# cpu.net
KiCad netlist of a schematic drawn in Altium Designer
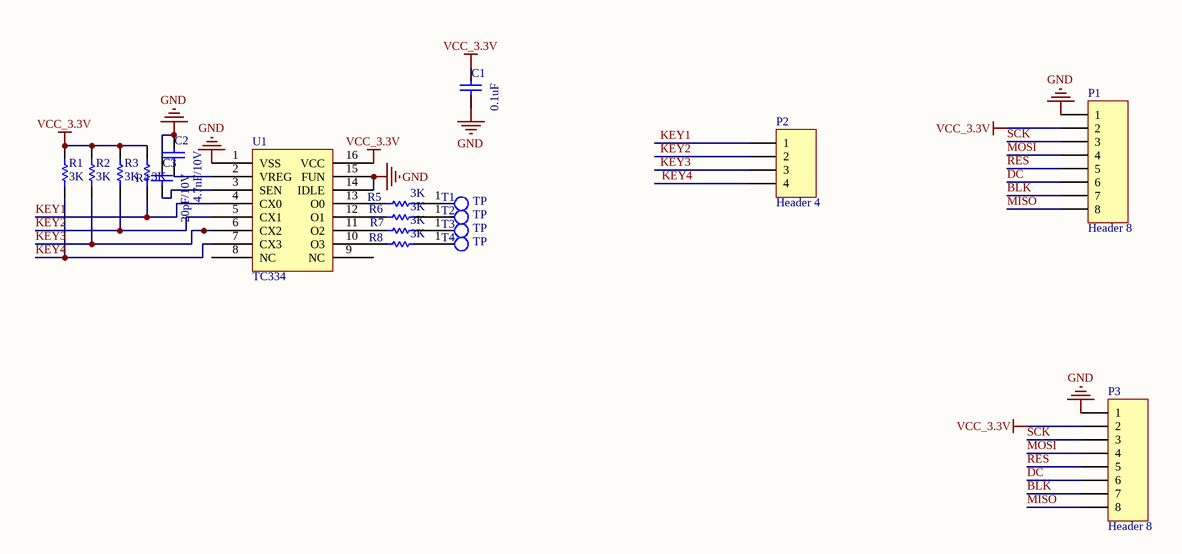
[diagram p0: cpu.SchDoc]

(export (version "E")
  (design (tool "Eeschema 10.0.6"))
  (components
    (comp (ref "C1")
      (value "0.1uF")
      (footprint "0603C")
      (description "Capacitor")
      (fields (field (name "PUBLISHER") "Altium Limited"))
      (libsource (lib "Miscellaneous Devices") (part "Cap"))
    )
    (comp (ref "C2")
      (value "4.7nF/10V")
      (footprint "0603C")
      (description "Capacitor")
      (fields (field (name "PUBLISHER") "Altium Limited"))
      (libsource (lib "Miscellaneous Devices") (part "Cap"))
    )
    (comp (ref "C3")
      (value "20pF/10V")
      (footprint "0603C")
      (description "Capacitor")
      (fields (field (name "PUBLISHER") "Altium Limited"))
      (libsource (lib "Miscellaneous Devices") (part "Cap"))
    )
    (comp (ref "P1")
      (value "Header 8")
      (footprint "HDR1X8")
      (description "Header, 8-Pin")
      (fields (field (name "PUBLISHER") "Altium Limited"))
      (libsource (lib "Miscellaneous Connectors") (part "Header 8"))
    )
    (comp (ref "P2")
      (value "Header 4")
      (footprint "HDR1X4")
      (description "Header, 4-Pin")
      (fields (field (name "PUBLISHER") "Altium Limited"))
      (libsource (lib "Miscellaneous Connectors") (part "Header 4"))
    )
    (comp (ref "P3")
      (value "Header 8")
      (footprint "TFT2.4")
      (description "Header, 8-Pin")
      (fields (field (name "PUBLISHER") "Altium Limited"))
      (libsource (lib "Miscellaneous Connectors") (part "Header 8"))
    )
    (comp (ref "R1")
      (value "3K")
      (footprint "0603R")
      (description "Semiconductor Resistor")
      (fields (field (name "PUBLISHER") "Altium Limited"))
      (libsource (lib "Miscellaneous Devices") (part "Res Semi"))
    )
    (comp (ref "R2")
      (value "3K")
      (footprint "0603R")
      (description "Semiconductor Resistor")
      (fields (field (name "PUBLISHER") "Altium Limited"))
      (libsource (lib "Miscellaneous Devices") (part "Res Semi"))
    )
    (comp (ref "R3")
      (value "3K")
      (footprint "0603R")
      (description "Semiconductor Resistor")
      (fields (field (name "PUBLISHER") "Altium Limited"))
      (libsource (lib "Miscellaneous Devices") (part "Res Semi"))
    )
    (comp (ref "R4")
      (value "3K")
      (footprint "0603R")
      (description "Semiconductor Resistor")
      (fields (field (name "PUBLISHER") "Altium Limited"))
      (libsource (lib "Miscellaneous Devices") (part "Res Semi"))
    )
    (comp (ref "R5")
      (value "3K")
      (footprint "0603R")
      (description "Semiconductor Resistor")
      (fields (field (name "PUBLISHER") "Altium Limited"))
      (libsource (lib "Miscellaneous Devices") (part "Res Semi"))
    )
    (comp (ref "R6")
      (value "3K")
      (footprint "0603R")
      (description "Semiconductor Resistor")
      (fields (field (name "PUBLISHER") "Altium Limited"))
      (libsource (lib "Miscellaneous Devices") (part "Res Semi"))
    )
    (comp (ref "R7")
      (value "3K")
      (footprint "0603R")
      (description "Semiconductor Resistor")
      (fields (field (name "PUBLISHER") "Altium Limited"))
      (libsource (lib "Miscellaneous Devices") (part "Res Semi"))
    )
    (comp (ref "R8")
      (value "3K")
      (footprint "0603R")
      (description "Semiconductor Resistor")
      (fields (field (name "PUBLISHER") "Altium Limited"))
      (libsource (lib "Miscellaneous Devices") (part "Res Semi"))
    )
    (comp (ref "T1") (value "TP") (footprint "TOUCH-PAD") (libsource (lib "Schlib_20110825") (part "TP")))
    (comp (ref "T2") (value "TP") (footprint "TOUCH-PAD") (libsource (lib "Schlib_20110825") (part "TP")))
    (comp (ref "T3") (value "TP") (footprint "TOUCH-PAD") (libsource (lib "Schlib_20110825") (part "TP")))
    (comp (ref "T4") (value "TP") (footprint "TOUCH-PAD") (libsource (lib "Schlib_20110825") (part "TP")))
    (comp (ref "U1")
      (value "TC334")
      (footprint "SOIC127P600X265-16N")
      (libsource (lib "Schlib_20110825") (part "TC334"))
    )
  )
  (nets
    (net (code "1") (name "/BLK") (class "Default")
      (node (ref "P1") (pin "7") (pinfunction "7_7") (pintype "passive"))
      (node (ref "P3") (pin "7") (pinfunction "7_7") (pintype "passive"))
    )
    (net (code "2") (name "/DC") (class "Default")
      (node (ref "P1") (pin "6") (pinfunction "6_6") (pintype "passive"))
      (node (ref "P3") (pin "6") (pinfunction "6_6") (pintype "passive"))
    )
    (net (code "3") (name "/KEY1") (class "Default")
      (node (ref "P2") (pin "1") (pinfunction "1_1") (pintype "passive"))
      (node (ref "R4") (pin "2") (pinfunction "2_2") (pintype "passive"))
      (node (ref "U1") (pin "4") (pinfunction "CX0_4") (pintype "passive"))
    )
    (net (code "4") (name "/KEY2") (class "Default")
      (node (ref "P2") (pin "2") (pinfunction "2_2") (pintype "passive"))
      (node (ref "R3") (pin "2") (pinfunction "2_2") (pintype "passive"))
      (node (ref "U1") (pin "5") (pinfunction "CX1_5") (pintype "passive"))
    )
    (net (code "5") (name "/KEY3") (class "Default")
      (node (ref "P2") (pin "3") (pinfunction "3_3") (pintype "passive"))
      (node (ref "R2") (pin "2") (pinfunction "2_2") (pintype "passive"))
      (node (ref "U1") (pin "6") (pinfunction "CX2_6") (pintype "passive"))
    )
    (net (code "6") (name "/KEY4") (class "Default")
      (node (ref "P2") (pin "4") (pinfunction "4_4") (pintype "passive"))
      (node (ref "R1") (pin "2") (pinfunction "2_2") (pintype "passive"))
      (node (ref "U1") (pin "7") (pinfunction "CX3_7") (pintype "passive"))
    )
    (net (code "7") (name "/MISO") (class "Default")
      (node (ref "P1") (pin "8") (pinfunction "8_8") (pintype "passive"))
      (node (ref "P3") (pin "8") (pinfunction "8_8") (pintype "passive"))
    )
    (net (code "8") (name "/MOSI") (class "Default")
      (node (ref "P1") (pin "4") (pinfunction "4_4") (pintype "passive"))
      (node (ref "P3") (pin "4") (pinfunction "4_4") (pintype "passive"))
    )
    (net (code "9") (name "/RES") (class "Default")
      (node (ref "P1") (pin "5") (pinfunction "5_5") (pintype "passive"))
      (node (ref "P3") (pin "5") (pinfunction "5_5") (pintype "passive"))
    )
    (net (code "10") (name "/SCK") (class "Default")
      (node (ref "P1") (pin "3") (pinfunction "3_3") (pintype "passive"))
      (node (ref "P3") (pin "3") (pinfunction "3_3") (pintype "passive"))
    )
    (net (code "11") (name "GND") (class "Default")
      (node (ref "C1") (pin "2") (pinfunction "2_2") (pintype "passive"))
      (node (ref "C2") (pin "1") (pinfunction "1_1") (pintype "passive"))
      (node (ref "C3") (pin "1") (pinfunction "1_1") (pintype "passive"))
      (node (ref "P1") (pin "1") (pinfunction "1_1") (pintype "passive"))
      (node (ref "P3") (pin "1") (pinfunction "1_1") (pintype "passive"))
      (node (ref "U1") (pin "1") (pinfunction "VSS_1") (pintype "passive"))
      (node (ref "U1") (pin "14") (pinfunction "IDLE_14") (pintype "passive"))
      (node (ref "U1") (pin "15") (pinfunction "FUN_15") (pintype "passive"))
    )
    (net (code "12") (name "Net-(R5-Pad1)") (class "Default")
      (node (ref "R5") (pin "1") (pinfunction "1_1") (pintype "passive"))
      (node (ref "T1") (pin "1") (pintype "passive"))
    )
    (net (code "13") (name "Net-(R6-Pad1)") (class "Default")
      (node (ref "R6") (pin "1") (pinfunction "1_1") (pintype "passive"))
      (node (ref "T2") (pin "1") (pintype "passive"))
    )
    (net (code "14") (name "Net-(R7-Pad1)") (class "Default")
      (node (ref "R7") (pin "1") (pinfunction "1_1") (pintype "passive"))
      (node (ref "T3") (pin "1") (pintype "passive"))
    )
    (net (code "15") (name "Net-(R8-Pad1)") (class "Default")
      (node (ref "R8") (pin "1") (pinfunction "1_1") (pintype "passive"))
      (node (ref "T4") (pin "1") (pintype "passive"))
    )
    (net (code "16") (name "Net-(U1-O0)") (class "Default")
      (node (ref "R5") (pin "2") (pinfunction "2_2") (pintype "passive"))
      (node (ref "U1") (pin "13") (pinfunction "O0_13") (pintype "passive"))
    )
    (net (code "17") (name "Net-(U1-O1)") (class "Default")
      (node (ref "R6") (pin "2") (pinfunction "2_2") (pintype "passive"))
      (node (ref "U1") (pin "12") (pinfunction "O1_12") (pintype "passive"))
    )
    (net (code "18") (name "Net-(U1-O2)") (class "Default")
      (node (ref "R7") (pin "2") (pinfunction "2_2") (pintype "passive"))
      (node (ref "U1") (pin "11") (pinfunction "O2_11") (pintype "passive"))
    )
    (net (code "19") (name "Net-(U1-O3)") (class "Default")
      (node (ref "R8") (pin "2") (pinfunction "2_2") (pintype "passive"))
      (node (ref "U1") (pin "10") (pinfunction "O3_10") (pintype "passive"))
    )
    (net (code "20") (name "Net-(U1-SEN)") (class "Default")
      (node (ref "C3") (pin "2") (pinfunction "2_2") (pintype "passive"))
      (node (ref "U1") (pin "3") (pinfunction "SEN_3") (pintype "passive"))
    )
    (net (code "21") (name "Net-(U1-VREG)") (class "Default")
      (node (ref "C2") (pin "2") (pinfunction "2_2") (pintype "passive"))
      (node (ref "U1") (pin "2") (pinfunction "VREG_2") (pintype "passive"))
    )
    (net (code "22") (name "VCC_3.3V") (class "Default")
      (node (ref "C1") (pin "1") (pinfunction "1_1") (pintype "passive"))
      (node (ref "P1") (pin "2") (pinfunction "2_2") (pintype "passive"))
      (node (ref "P3") (pin "2") (pinfunction "2_2") (pintype "passive"))
      (node (ref "R1") (pin "1") (pinfunction "1_1") (pintype "passive"))
      (node (ref "R2") (pin "1") (pinfunction "1_1") (pintype "passive"))
      (node (ref "R3") (pin "1") (pinfunction "1_1") (pintype "passive"))
      (node (ref "R4") (pin "1") (pinfunction "1_1") (pintype "passive"))
      (node (ref "U1") (pin "16") (pinfunction "VCC_16") (pintype "passive"))
    )
    (net (code "23") (name "unconnected-(U1-NC-Pad8)") (class "Default")
      (node (ref "U1") (pin "8") (pinfunction "NC_8") (pintype "passive"))
    )
    (net (code "24") (name "unconnected-(U1-NC-Pad9)") (class "Default")
      (node (ref "U1") (pin "9") (pinfunction "NC_9") (pintype "passive"))
    )
  )
)
